# M307-9601.net
KiCad netlist of a schematic drawn in EAGLE
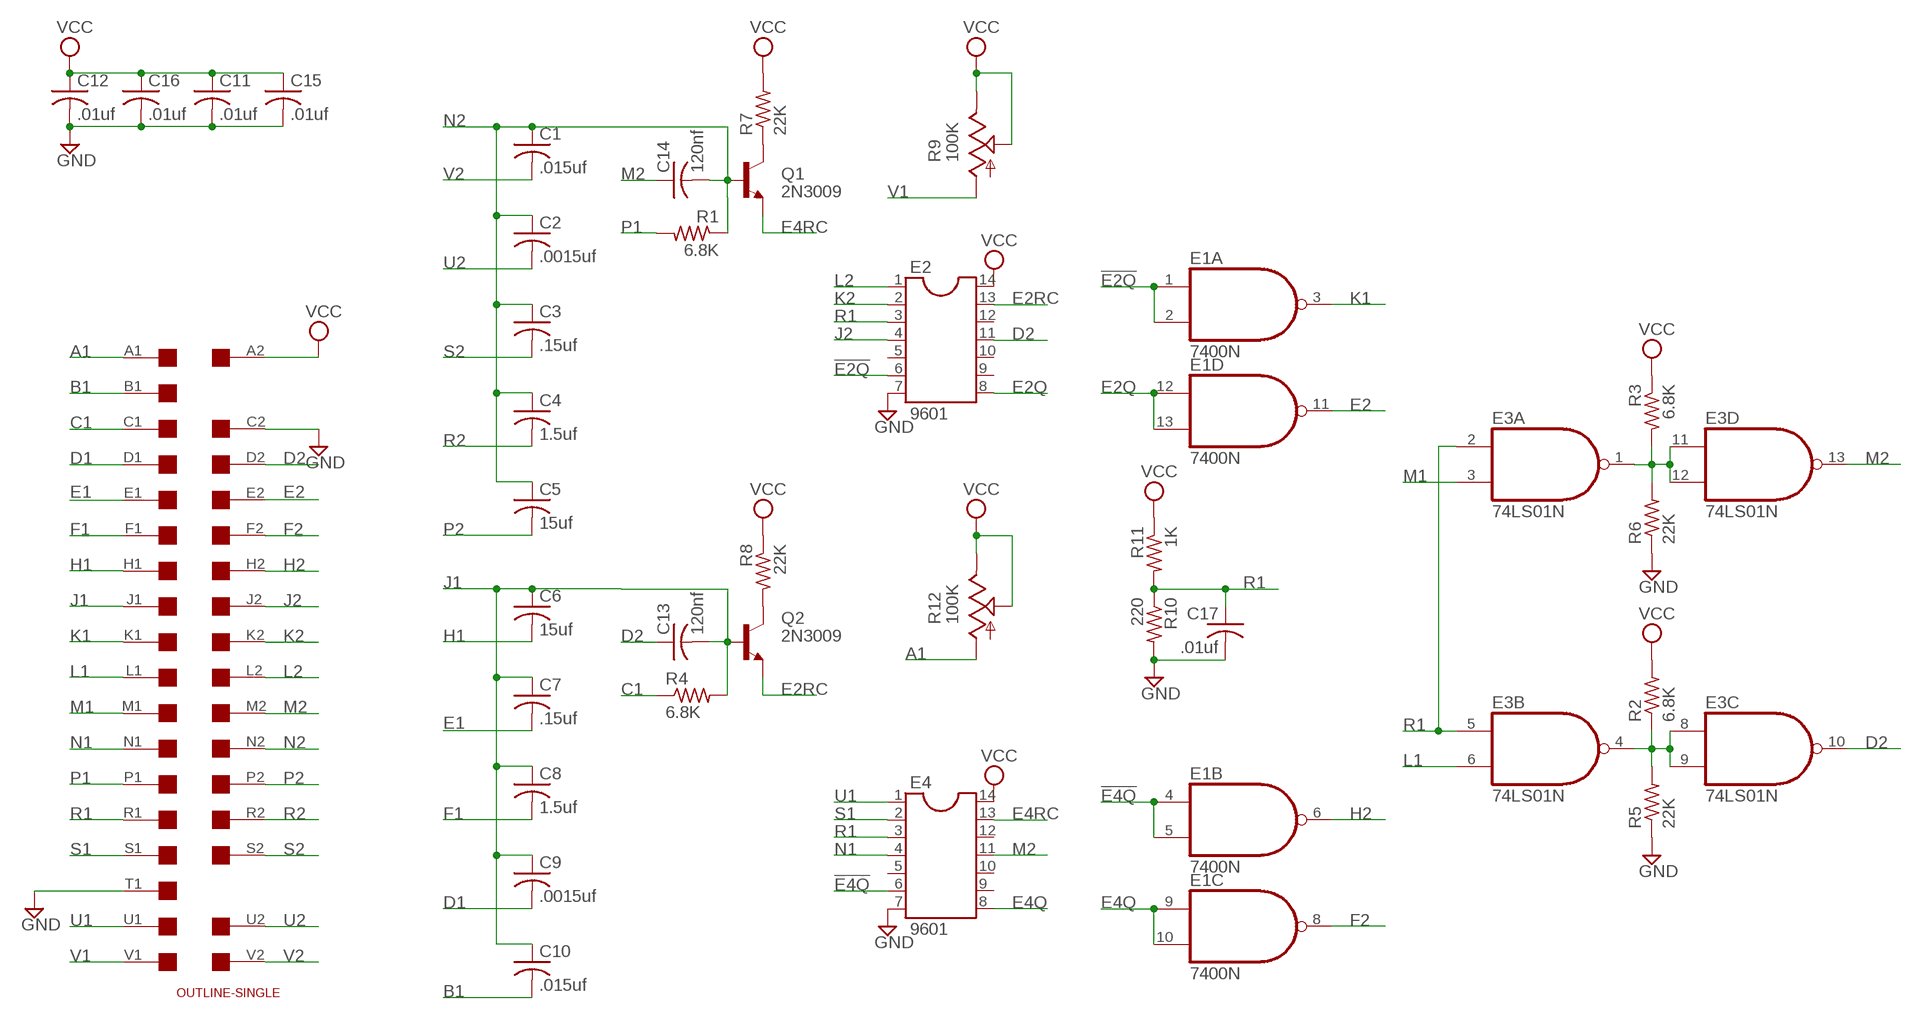
[diagram p0: schematic, sheet 1]

(export (version "E")
  (design (tool "Eeschema 10.0.6"))
  (components
    (comp (ref "C1")
      (value ".015uf")
      (footprint "eagle-import:C150-054X183")
      (libsource (lib "eagle-import") (part "C-US150-054X183"))
    )
    (comp (ref "C2")
      (value ".0015uf")
      (footprint "eagle-import:C050-025X075")
      (libsource (lib "eagle-import") (part "C-US050-025X075"))
    )
    (comp (ref "C3")
      (value ".15uf")
      (footprint "eagle-import:C102-043X133")
      (libsource (lib "eagle-import") (part "C-US102-043X133"))
    )
    (comp (ref "C4")
      (value "1.5uf")
      (footprint "eagle-import:C150-054X183")
      (libsource (lib "eagle-import") (part "C-US150-054X183"))
    )
    (comp (ref "C5")
      (value "15uf")
      (footprint "eagle-import:C150-054X183")
      (libsource (lib "eagle-import") (part "C-US150-054X183"))
    )
    (comp (ref "C6")
      (value "15uf")
      (footprint "eagle-import:C150-054X183")
      (libsource (lib "eagle-import") (part "C-US150-054X183"))
    )
    (comp (ref "C7")
      (value ".15uf")
      (footprint "eagle-import:C102-043X133")
      (libsource (lib "eagle-import") (part "C-US102-043X133"))
    )
    (comp (ref "C8")
      (value "1.5uf")
      (footprint "eagle-import:C150-054X183")
      (libsource (lib "eagle-import") (part "C-US150-054X183"))
    )
    (comp (ref "C9")
      (value ".0015uf")
      (footprint "eagle-import:C050-025X075")
      (libsource (lib "eagle-import") (part "C-US050-025X075"))
    )
    (comp (ref "C10")
      (value ".015uf")
      (footprint "eagle-import:C150-054X183")
      (libsource (lib "eagle-import") (part "C-US150-054X183"))
    )
    (comp (ref "C11")
      (value ".01uf")
      (footprint "eagle-import:C050-025X075")
      (libsource (lib "eagle-import") (part "C-US050-025X075"))
    )
    (comp (ref "C12")
      (value ".01uf")
      (footprint "eagle-import:C050-025X075")
      (libsource (lib "eagle-import") (part "C-US050-025X075"))
    )
    (comp (ref "C13")
      (value "120nf")
      (footprint "eagle-import:C075-032X103")
      (libsource (lib "eagle-import") (part "C-US075-032X103"))
    )
    (comp (ref "C14")
      (value "120nf")
      (footprint "eagle-import:C075-032X103")
      (libsource (lib "eagle-import") (part "C-US075-032X103"))
    )
    (comp (ref "C15")
      (value ".01uf")
      (footprint "eagle-import:C050-025X075")
      (libsource (lib "eagle-import") (part "C-US050-025X075"))
    )
    (comp (ref "C16")
      (value ".01uf")
      (footprint "eagle-import:C050-025X075")
      (libsource (lib "eagle-import") (part "C-US050-025X075"))
    )
    (comp (ref "C17")
      (value ".01uf")
      (footprint "eagle-import:C050-025X075")
      (libsource (lib "eagle-import") (part "C-US050-025X075"))
    )
    (comp (ref "E1")
      (value "7400N")
      (footprint "eagle-import:DIL14")
      (libsource (lib "eagle-import") (part "7400N"))
    )
    (comp (ref "E2")
      (value "9601")
      (footprint "eagle-import:DIL14")
      (libsource (lib "eagle-import") (part "DIL14"))
    )
    (comp (ref "E3")
      (value "74LS01N")
      (footprint "eagle-import:DIL14")
      (libsource (lib "eagle-import") (part "7401NLS"))
    )
    (comp (ref "E4")
      (value "9601")
      (footprint "eagle-import:DIL14")
      (libsource (lib "eagle-import") (part "DIL14"))
    )
    (comp (ref "Q1")
      (value "2N3009")
      (footprint "eagle-import:TO39")
      (libsource (lib "eagle-import") (part "-NPN-TO39-EBC2N3019"))
    )
    (comp (ref "Q2")
      (value "2N3009")
      (footprint "eagle-import:TO39")
      (libsource (lib "eagle-import") (part "-NPN-TO39-EBC2N3019"))
    )
    (comp (ref "R1")
      (value "6.8K")
      (footprint "eagle-import:0207_10")
      (libsource (lib "eagle-import") (part "R-US_0207/10"))
    )
    (comp (ref "R2")
      (value "6.8K")
      (footprint "eagle-import:0207_10")
      (libsource (lib "eagle-import") (part "R-US_0207/10"))
    )
    (comp (ref "R3")
      (value "6.8K")
      (footprint "eagle-import:0207_10")
      (libsource (lib "eagle-import") (part "R-US_0207/10"))
    )
    (comp (ref "R4")
      (value "6.8K")
      (footprint "eagle-import:0207_10")
      (libsource (lib "eagle-import") (part "R-US_0207/10"))
    )
    (comp (ref "R5")
      (value "22K")
      (footprint "eagle-import:0207_10")
      (libsource (lib "eagle-import") (part "R-US_0207/10"))
    )
    (comp (ref "R6")
      (value "22K")
      (footprint "eagle-import:0207_10")
      (libsource (lib "eagle-import") (part "R-US_0207/10"))
    )
    (comp (ref "R7")
      (value "22K")
      (footprint "eagle-import:0207_10")
      (libsource (lib "eagle-import") (part "R-US_0207/10"))
    )
    (comp (ref "R8")
      (value "22K")
      (footprint "eagle-import:0207_10")
      (libsource (lib "eagle-import") (part "R-US_0207/10"))
    )
    (comp (ref "R9")
      (value "100K")
      (footprint "eagle-import:PT-SPIN")
      (libsource (lib "eagle-import") (part "TRIM_US-PTSPIN"))
    )
    (comp (ref "R10")
      (value "220")
      (footprint "eagle-import:0207_10")
      (libsource (lib "eagle-import") (part "R-US_0207/10"))
    )
    (comp (ref "R11")
      (value "1K")
      (footprint "eagle-import:0207_10")
      (libsource (lib "eagle-import") (part "R-US_0207/10"))
    )
    (comp (ref "R12")
      (value "100K")
      (footprint "eagle-import:PT-SPIN")
      (libsource (lib "eagle-import") (part "TRIM_US-PTSPIN"))
    )
    (comp (ref "U$1")
      (value "OUTLINE-SINGLE")
      (footprint "eagle-import:SINGLE")
      (libsource (lib "eagle-import") (part "OUTLINE-SINGLE"))
    )
    (comp (ref "U$4")
      (value "SINGLE")
      (footprint "eagle-import:EDGE-CON2")
      (libsource (lib "eagle-import") (part "SINGLE"))
    )
  )
  (nets
    (net (code "1") (name "/A1") (class "Default")
      (node (ref "R12") (pin "A") (pinfunction "A_A") (pintype "passive"))
      (node (ref "U$4") (pin "A1") (pinfunction "1_A1") (pintype "bidirectional"))
    )
    (net (code "2") (name "/B1") (class "Default")
      (node (ref "C10") (pin "2") (pinfunction "2_2") (pintype "passive"))
      (node (ref "U$4") (pin "B1") (pinfunction "1_B1") (pintype "bidirectional"))
    )
    (net (code "3") (name "/C1") (class "Default")
      (node (ref "R4") (pin "1") (pinfunction "1_1") (pintype "passive"))
      (node (ref "U$4") (pin "C1") (pinfunction "1_C1") (pintype "bidirectional"))
    )
    (net (code "4") (name "/D1") (class "Default")
      (node (ref "C9") (pin "2") (pinfunction "2_2") (pintype "passive"))
      (node (ref "U$4") (pin "D1") (pinfunction "1_D1") (pintype "bidirectional"))
    )
    (net (code "5") (name "/D2") (class "Default")
      (node (ref "C13") (pin "1") (pinfunction "1_1") (pintype "passive"))
      (node (ref "E2") (pin "11") (pinfunction "11_11") (pintype "passive"))
      (node (ref "E3") (pin "10") (pinfunction "O_10") (pintype "open_collector"))
      (node (ref "U$4") (pin "D2") (pinfunction "1_D2") (pintype "bidirectional"))
    )
    (net (code "6") (name "/E1") (class "Default")
      (node (ref "C7") (pin "2") (pinfunction "2_2") (pintype "passive"))
      (node (ref "U$4") (pin "E1") (pinfunction "1_E1") (pintype "bidirectional"))
    )
    (net (code "7") (name "/E2") (class "Default")
      (node (ref "E1") (pin "11") (pinfunction "O_11") (pintype "output"))
      (node (ref "U$4") (pin "E2") (pinfunction "1_E2") (pintype "bidirectional"))
    )
    (net (code "8") (name "/E2Q") (class "Default")
      (node (ref "E1") (pin "12") (pinfunction "I0_12") (pintype "input"))
      (node (ref "E1") (pin "13") (pinfunction "I1_13") (pintype "input"))
      (node (ref "E2") (pin "8") (pinfunction "8_8") (pintype "passive"))
    )
    (net (code "9") (name "/E2RC") (class "Default")
      (node (ref "E2") (pin "13") (pinfunction "13_13") (pintype "passive"))
      (node (ref "Q2") (pin "1") (pinfunction "E_1") (pintype "passive"))
    )
    (net (code "10") (name "/E4Q") (class "Default")
      (node (ref "E1") (pin "10") (pinfunction "I1_10") (pintype "input"))
      (node (ref "E1") (pin "9") (pinfunction "I0_9") (pintype "input"))
      (node (ref "E4") (pin "8") (pinfunction "8_8") (pintype "passive"))
    )
    (net (code "11") (name "/E4RC") (class "Default")
      (node (ref "E4") (pin "13") (pinfunction "13_13") (pintype "passive"))
      (node (ref "Q1") (pin "1") (pinfunction "E_1") (pintype "passive"))
    )
    (net (code "12") (name "/F1") (class "Default")
      (node (ref "C8") (pin "2") (pinfunction "2_2") (pintype "passive"))
      (node (ref "U$4") (pin "F1") (pinfunction "1_F1") (pintype "bidirectional"))
    )
    (net (code "13") (name "/F2") (class "Default")
      (node (ref "E1") (pin "8") (pinfunction "O_8") (pintype "output"))
      (node (ref "U$4") (pin "F2") (pinfunction "1_F2") (pintype "bidirectional"))
    )
    (net (code "14") (name "/H1") (class "Default")
      (node (ref "C6") (pin "2") (pinfunction "2_2") (pintype "passive"))
      (node (ref "U$4") (pin "H1") (pinfunction "1_H1") (pintype "bidirectional"))
    )
    (net (code "15") (name "/H2") (class "Default")
      (node (ref "E1") (pin "6") (pinfunction "O_6") (pintype "output"))
      (node (ref "U$4") (pin "H2") (pinfunction "1_H2") (pintype "bidirectional"))
    )
    (net (code "16") (name "/J1") (class "Default")
      (node (ref "C10") (pin "1") (pinfunction "1_1") (pintype "passive"))
      (node (ref "C13") (pin "2") (pinfunction "2_2") (pintype "passive"))
      (node (ref "C6") (pin "1") (pinfunction "1_1") (pintype "passive"))
      (node (ref "C7") (pin "1") (pinfunction "1_1") (pintype "passive"))
      (node (ref "C8") (pin "1") (pinfunction "1_1") (pintype "passive"))
      (node (ref "C9") (pin "1") (pinfunction "1_1") (pintype "passive"))
      (node (ref "Q2") (pin "2") (pinfunction "B_2") (pintype "passive"))
      (node (ref "R4") (pin "2") (pinfunction "2_2") (pintype "passive"))
      (node (ref "U$4") (pin "J1") (pinfunction "1_J1") (pintype "bidirectional"))
    )
    (net (code "17") (name "/J2") (class "Default")
      (node (ref "E2") (pin "4") (pinfunction "4_4") (pintype "passive"))
      (node (ref "U$4") (pin "J2") (pinfunction "1_J2") (pintype "bidirectional"))
    )
    (net (code "18") (name "/K1") (class "Default")
      (node (ref "E1") (pin "3") (pinfunction "O_3") (pintype "output"))
      (node (ref "U$4") (pin "K1") (pinfunction "1_K1") (pintype "bidirectional"))
    )
    (net (code "19") (name "/K2") (class "Default")
      (node (ref "E2") (pin "2") (pinfunction "2_2") (pintype "passive"))
      (node (ref "U$4") (pin "K2") (pinfunction "1_K2") (pintype "bidirectional"))
    )
    (net (code "20") (name "/L1") (class "Default")
      (node (ref "E3") (pin "6") (pinfunction "I1_6") (pintype "input"))
      (node (ref "U$4") (pin "L1") (pinfunction "1_L1") (pintype "bidirectional"))
    )
    (net (code "21") (name "/L2") (class "Default")
      (node (ref "E2") (pin "1") (pinfunction "1_1") (pintype "passive"))
      (node (ref "U$4") (pin "L2") (pinfunction "1_L2") (pintype "bidirectional"))
    )
    (net (code "22") (name "/M1") (class "Default")
      (node (ref "E3") (pin "3") (pinfunction "I1_3") (pintype "input"))
      (node (ref "U$4") (pin "M1") (pinfunction "1_M1") (pintype "bidirectional"))
    )
    (net (code "23") (name "/M2") (class "Default")
      (node (ref "C14") (pin "1") (pinfunction "1_1") (pintype "passive"))
      (node (ref "E3") (pin "13") (pinfunction "O_13") (pintype "open_collector"))
      (node (ref "E4") (pin "11") (pinfunction "11_11") (pintype "passive"))
      (node (ref "U$4") (pin "M2") (pinfunction "1_M2") (pintype "bidirectional"))
    )
    (net (code "24") (name "/N1") (class "Default")
      (node (ref "E4") (pin "4") (pinfunction "4_4") (pintype "passive"))
      (node (ref "U$4") (pin "N1") (pinfunction "1_N1") (pintype "bidirectional"))
    )
    (net (code "25") (name "/N2") (class "Default")
      (node (ref "C1") (pin "1") (pinfunction "1_1") (pintype "passive"))
      (node (ref "C14") (pin "2") (pinfunction "2_2") (pintype "passive"))
      (node (ref "C2") (pin "1") (pinfunction "1_1") (pintype "passive"))
      (node (ref "C3") (pin "1") (pinfunction "1_1") (pintype "passive"))
      (node (ref "C4") (pin "1") (pinfunction "1_1") (pintype "passive"))
      (node (ref "C5") (pin "1") (pinfunction "1_1") (pintype "passive"))
      (node (ref "Q1") (pin "2") (pinfunction "B_2") (pintype "passive"))
      (node (ref "R1") (pin "1") (pinfunction "1_1") (pintype "passive"))
      (node (ref "U$4") (pin "N2") (pinfunction "1_N2") (pintype "bidirectional"))
    )
    (net (code "26") (name "/P1") (class "Default")
      (node (ref "R1") (pin "2") (pinfunction "2_2") (pintype "passive"))
      (node (ref "U$4") (pin "P1") (pinfunction "1_P1") (pintype "bidirectional"))
    )
    (net (code "27") (name "/P2") (class "Default")
      (node (ref "C5") (pin "2") (pinfunction "2_2") (pintype "passive"))
      (node (ref "U$4") (pin "P2") (pinfunction "1_P2") (pintype "bidirectional"))
    )
    (net (code "28") (name "/R1") (class "Default")
      (node (ref "C17") (pin "1") (pinfunction "1_1") (pintype "passive"))
      (node (ref "E2") (pin "3") (pinfunction "3_3") (pintype "passive"))
      (node (ref "E3") (pin "2") (pinfunction "I0_2") (pintype "input"))
      (node (ref "E3") (pin "5") (pinfunction "I0_5") (pintype "input"))
      (node (ref "E4") (pin "3") (pinfunction "3_3") (pintype "passive"))
      (node (ref "R10") (pin "1") (pinfunction "1_1") (pintype "passive"))
      (node (ref "R11") (pin "2") (pinfunction "2_2") (pintype "passive"))
      (node (ref "U$4") (pin "R1") (pinfunction "1_R1") (pintype "bidirectional"))
    )
    (net (code "29") (name "/R2") (class "Default")
      (node (ref "C4") (pin "2") (pinfunction "2_2") (pintype "passive"))
      (node (ref "U$4") (pin "R2") (pinfunction "1_R2") (pintype "bidirectional"))
    )
    (net (code "30") (name "/S1") (class "Default")
      (node (ref "E4") (pin "2") (pinfunction "2_2") (pintype "passive"))
      (node (ref "U$4") (pin "S1") (pinfunction "1_S1") (pintype "bidirectional"))
    )
    (net (code "31") (name "/S2") (class "Default")
      (node (ref "C3") (pin "2") (pinfunction "2_2") (pintype "passive"))
      (node (ref "U$4") (pin "S2") (pinfunction "1_S2") (pintype "bidirectional"))
    )
    (net (code "32") (name "/U1") (class "Default")
      (node (ref "E4") (pin "1") (pinfunction "1_1") (pintype "passive"))
      (node (ref "U$4") (pin "U1") (pinfunction "1_U1") (pintype "bidirectional"))
    )
    (net (code "33") (name "/U2") (class "Default")
      (node (ref "C2") (pin "2") (pinfunction "2_2") (pintype "passive"))
      (node (ref "U$4") (pin "U2") (pinfunction "1_U2") (pintype "bidirectional"))
    )
    (net (code "34") (name "/V1") (class "Default")
      (node (ref "R9") (pin "A") (pinfunction "A_A") (pintype "passive"))
      (node (ref "U$4") (pin "V1") (pinfunction "1_V1") (pintype "bidirectional"))
    )
    (net (code "35") (name "/V2") (class "Default")
      (node (ref "C1") (pin "2") (pinfunction "2_2") (pintype "passive"))
      (node (ref "U$4") (pin "V2") (pinfunction "1_V2") (pintype "bidirectional"))
    )
    (net (code "36") (name "/~{E2Q}") (class "Default")
      (node (ref "E1") (pin "1") (pinfunction "I0_1") (pintype "input"))
      (node (ref "E1") (pin "2") (pinfunction "I1_2") (pintype "input"))
      (node (ref "E2") (pin "6") (pinfunction "6_6") (pintype "passive"))
    )
    (net (code "37") (name "/~{E4Q}") (class "Default")
      (node (ref "E1") (pin "4") (pinfunction "I0_4") (pintype "input"))
      (node (ref "E1") (pin "5") (pinfunction "I1_5") (pintype "input"))
      (node (ref "E4") (pin "6") (pinfunction "6_6") (pintype "passive"))
    )
    (net (code "38") (name "GND") (class "Default")
      (node (ref "C11") (pin "2") (pinfunction "2_2") (pintype "passive"))
      (node (ref "C12") (pin "2") (pinfunction "2_2") (pintype "passive"))
      (node (ref "C15") (pin "2") (pinfunction "2_2") (pintype "passive"))
      (node (ref "C16") (pin "2") (pinfunction "2_2") (pintype "passive"))
      (node (ref "C17") (pin "2") (pinfunction "2_2") (pintype "passive"))
      (node (ref "E2") (pin "7") (pinfunction "7_7") (pintype "passive"))
      (node (ref "E4") (pin "7") (pinfunction "7_7") (pintype "passive"))
      (node (ref "R10") (pin "2") (pinfunction "2_2") (pintype "passive"))
      (node (ref "R5") (pin "1") (pinfunction "1_1") (pintype "passive"))
      (node (ref "R6") (pin "1") (pinfunction "1_1") (pintype "passive"))
      (node (ref "U$4") (pin "C2") (pinfunction "1_C2") (pintype "bidirectional"))
      (node (ref "U$4") (pin "T1") (pinfunction "1_T1") (pintype "bidirectional"))
    )
    (net (code "39") (name "Net-(E3A-O)") (class "Default")
      (node (ref "E3") (pin "1") (pinfunction "O_1") (pintype "open_collector"))
      (node (ref "E3") (pin "11") (pinfunction "I0_11") (pintype "input"))
      (node (ref "E3") (pin "12") (pinfunction "I1_12") (pintype "input"))
      (node (ref "R3") (pin "2") (pinfunction "2_2") (pintype "passive"))
      (node (ref "R6") (pin "2") (pinfunction "2_2") (pintype "passive"))
    )
    (net (code "40") (name "Net-(E3B-O)") (class "Default")
      (node (ref "E3") (pin "4") (pinfunction "O_4") (pintype "open_collector"))
      (node (ref "E3") (pin "8") (pinfunction "I0_8") (pintype "input"))
      (node (ref "E3") (pin "9") (pinfunction "I1_9") (pintype "input"))
      (node (ref "R2") (pin "1") (pinfunction "1_1") (pintype "passive"))
      (node (ref "R5") (pin "2") (pinfunction "2_2") (pintype "passive"))
    )
    (net (code "41") (name "Net-(Q1-C)") (class "Default")
      (node (ref "Q1") (pin "3") (pinfunction "C_3") (pintype "passive"))
      (node (ref "R7") (pin "1") (pinfunction "1_1") (pintype "passive"))
    )
    (net (code "42") (name "Net-(Q2-C)") (class "Default")
      (node (ref "Q2") (pin "3") (pinfunction "C_3") (pintype "passive"))
      (node (ref "R8") (pin "2") (pinfunction "2_2") (pintype "passive"))
    )
    (net (code "43") (name "VCC") (class "Default")
      (node (ref "C11") (pin "1") (pinfunction "1_1") (pintype "passive"))
      (node (ref "C12") (pin "1") (pinfunction "1_1") (pintype "passive"))
      (node (ref "C15") (pin "1") (pinfunction "1_1") (pintype "passive"))
      (node (ref "C16") (pin "1") (pinfunction "1_1") (pintype "passive"))
      (node (ref "E2") (pin "14") (pinfunction "14_14") (pintype "passive"))
      (node (ref "E4") (pin "14") (pinfunction "14_14") (pintype "passive"))
      (node (ref "R11") (pin "1") (pinfunction "1_1") (pintype "passive"))
      (node (ref "R12") (pin "E") (pinfunction "E_E") (pintype "passive"))
      (node (ref "R12") (pin "S") (pinfunction "S_S") (pintype "passive"))
      (node (ref "R2") (pin "2") (pinfunction "2_2") (pintype "passive"))
      (node (ref "R3") (pin "1") (pinfunction "1_1") (pintype "passive"))
      (node (ref "R7") (pin "2") (pinfunction "2_2") (pintype "passive"))
      (node (ref "R8") (pin "1") (pinfunction "1_1") (pintype "passive"))
      (node (ref "R9") (pin "E") (pinfunction "E_E") (pintype "passive"))
      (node (ref "R9") (pin "S") (pinfunction "S_S") (pintype "passive"))
      (node (ref "U$4") (pin "A2") (pinfunction "1_A2") (pintype "bidirectional"))
    )
    (net (code "44") (name "unconnected-(E2-Pad5)") (class "Default")
      (node (ref "E2") (pin "5") (pinfunction "5_5") (pintype "passive"))
    )
    (net (code "45") (name "unconnected-(E2-Pad9)") (class "Default")
      (node (ref "E2") (pin "9") (pinfunction "9_9") (pintype "passive"))
    )
    (net (code "46") (name "unconnected-(E2-Pad10)") (class "Default")
      (node (ref "E2") (pin "10") (pinfunction "10_10") (pintype "passive"))
    )
    (net (code "47") (name "unconnected-(E2-Pad12)") (class "Default")
      (node (ref "E2") (pin "12") (pinfunction "12_12") (pintype "passive"))
    )
    (net (code "48") (name "unconnected-(E4-Pad5)") (class "Default")
      (node (ref "E4") (pin "5") (pinfunction "5_5") (pintype "passive"))
    )
    (net (code "49") (name "unconnected-(E4-Pad9)") (class "Default")
      (node (ref "E4") (pin "9") (pinfunction "9_9") (pintype "passive"))
    )
    (net (code "50") (name "unconnected-(E4-Pad10)") (class "Default")
      (node (ref "E4") (pin "10") (pinfunction "10_10") (pintype "passive"))
    )
    (net (code "51") (name "unconnected-(E4-Pad12)") (class "Default")
      (node (ref "E4") (pin "12") (pinfunction "12_12") (pintype "passive"))
    )
  )
)
